# PMOD_Debug_-_CR6QEG.net
KiCad netlist of a schematic drawn in EAGLE
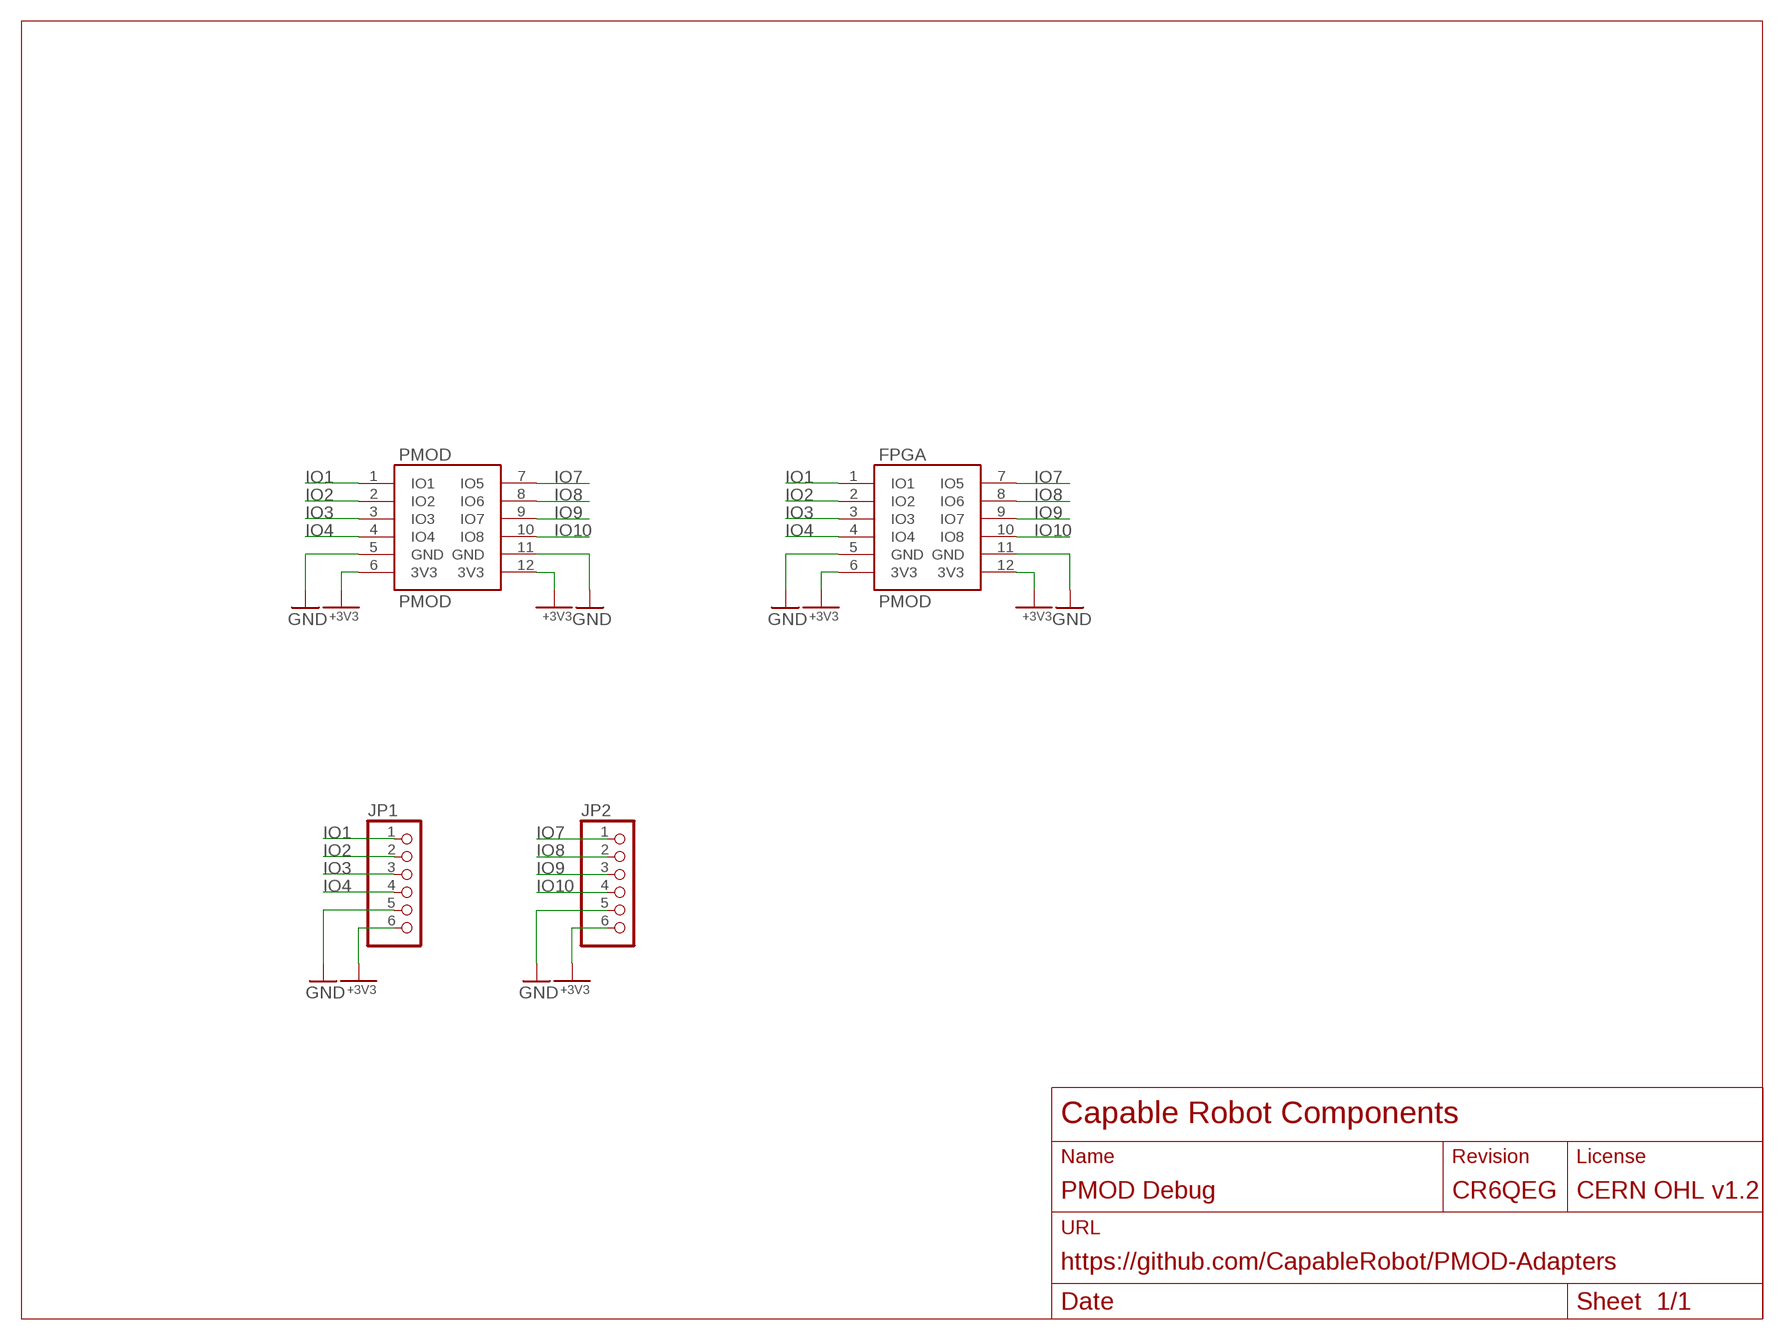
[diagram p0: schematic, sheet 1]

(export (version "E")
  (design (tool "Eeschema 10.0.6"))
  (components
    (comp (ref "FPGA")
      (value "PMOD-PERIPH")
      (footprint "eagle-import:HDRRA12W64P254_2X6_1524X254X556B")
      (libsource (lib "eagle-import") (part "PMOD-PERIPH"))
    )
    (comp (ref "JP1")
      (value "PINHD-1X6")
      (footprint "eagle-import:1X06")
      (libsource (lib "eagle-import") (part "PINHD-1X6"))
    )
    (comp (ref "JP2")
      (value "PINHD-1X6")
      (footprint "eagle-import:1X06")
      (libsource (lib "eagle-import") (part "PINHD-1X6"))
    )
    (comp (ref "PMOD")
      (value "PMOD-HOST")
      (footprint "eagle-import:HDRRAR12W64P254_2X6_1524X736X556B")
      (libsource (lib "eagle-import") (part "PMOD-HOST"))
    )
  )
  (nets
    (net (code "1") (name "+3V3") (class "Default")
      (node (ref "FPGA") (pin "12") (pinfunction "3V3_12") (pintype "bidirectional"))
      (node (ref "FPGA") (pin "6") (pinfunction "3V3_6") (pintype "bidirectional"))
      (node (ref "JP1") (pin "6") (pinfunction "6_6") (pintype "passive"))
      (node (ref "JP2") (pin "6") (pinfunction "6_6") (pintype "passive"))
      (node (ref "PMOD") (pin "12") (pinfunction "3V3_12") (pintype "bidirectional"))
      (node (ref "PMOD") (pin "6") (pinfunction "3V3_6") (pintype "bidirectional"))
    )
    (net (code "2") (name "/IO1") (class "Default")
      (node (ref "FPGA") (pin "1") (pinfunction "IO1_1") (pintype "bidirectional"))
      (node (ref "JP1") (pin "1") (pinfunction "1_1") (pintype "passive"))
      (node (ref "PMOD") (pin "1") (pinfunction "IO1_1") (pintype "bidirectional"))
    )
    (net (code "3") (name "/IO2") (class "Default")
      (node (ref "FPGA") (pin "2") (pinfunction "IO2_2") (pintype "bidirectional"))
      (node (ref "JP1") (pin "2") (pinfunction "2_2") (pintype "passive"))
      (node (ref "PMOD") (pin "2") (pinfunction "IO2_2") (pintype "bidirectional"))
    )
    (net (code "4") (name "/IO3") (class "Default")
      (node (ref "FPGA") (pin "3") (pinfunction "IO3_3") (pintype "bidirectional"))
      (node (ref "JP1") (pin "3") (pinfunction "3_3") (pintype "passive"))
      (node (ref "PMOD") (pin "3") (pinfunction "IO3_3") (pintype "bidirectional"))
    )
    (net (code "5") (name "/IO4") (class "Default")
      (node (ref "FPGA") (pin "4") (pinfunction "IO4_4") (pintype "bidirectional"))
      (node (ref "JP1") (pin "4") (pinfunction "4_4") (pintype "passive"))
      (node (ref "PMOD") (pin "4") (pinfunction "IO4_4") (pintype "bidirectional"))
    )
    (net (code "6") (name "/IO7") (class "Default")
      (node (ref "FPGA") (pin "7") (pinfunction "IO5_7") (pintype "bidirectional"))
      (node (ref "JP2") (pin "1") (pinfunction "1_1") (pintype "passive"))
      (node (ref "PMOD") (pin "7") (pinfunction "IO5_7") (pintype "bidirectional"))
    )
    (net (code "7") (name "/IO8") (class "Default")
      (node (ref "FPGA") (pin "8") (pinfunction "IO6_8") (pintype "bidirectional"))
      (node (ref "JP2") (pin "2") (pinfunction "2_2") (pintype "passive"))
      (node (ref "PMOD") (pin "8") (pinfunction "IO6_8") (pintype "bidirectional"))
    )
    (net (code "8") (name "/IO9") (class "Default")
      (node (ref "FPGA") (pin "9") (pinfunction "IO7_9") (pintype "bidirectional"))
      (node (ref "JP2") (pin "3") (pinfunction "3_3") (pintype "passive"))
      (node (ref "PMOD") (pin "9") (pinfunction "IO7_9") (pintype "bidirectional"))
    )
    (net (code "9") (name "/IO10") (class "Default")
      (node (ref "FPGA") (pin "10") (pinfunction "IO8_10") (pintype "bidirectional"))
      (node (ref "JP2") (pin "4") (pinfunction "4_4") (pintype "passive"))
      (node (ref "PMOD") (pin "10") (pinfunction "IO8_10") (pintype "bidirectional"))
    )
    (net (code "10") (name "GND") (class "Default")
      (node (ref "FPGA") (pin "11") (pinfunction "GND_11") (pintype "bidirectional"))
      (node (ref "FPGA") (pin "5") (pinfunction "GND_5") (pintype "bidirectional"))
      (node (ref "JP1") (pin "5") (pinfunction "5_5") (pintype "passive"))
      (node (ref "JP2") (pin "5") (pinfunction "5_5") (pintype "passive"))
      (node (ref "PMOD") (pin "11") (pinfunction "GND_11") (pintype "bidirectional"))
      (node (ref "PMOD") (pin "5") (pinfunction "GND_5") (pintype "bidirectional"))
    )
  )
)
